# sds3_pcb_rev1.net
KiCad netlist of a schematic drawn in EAGLE
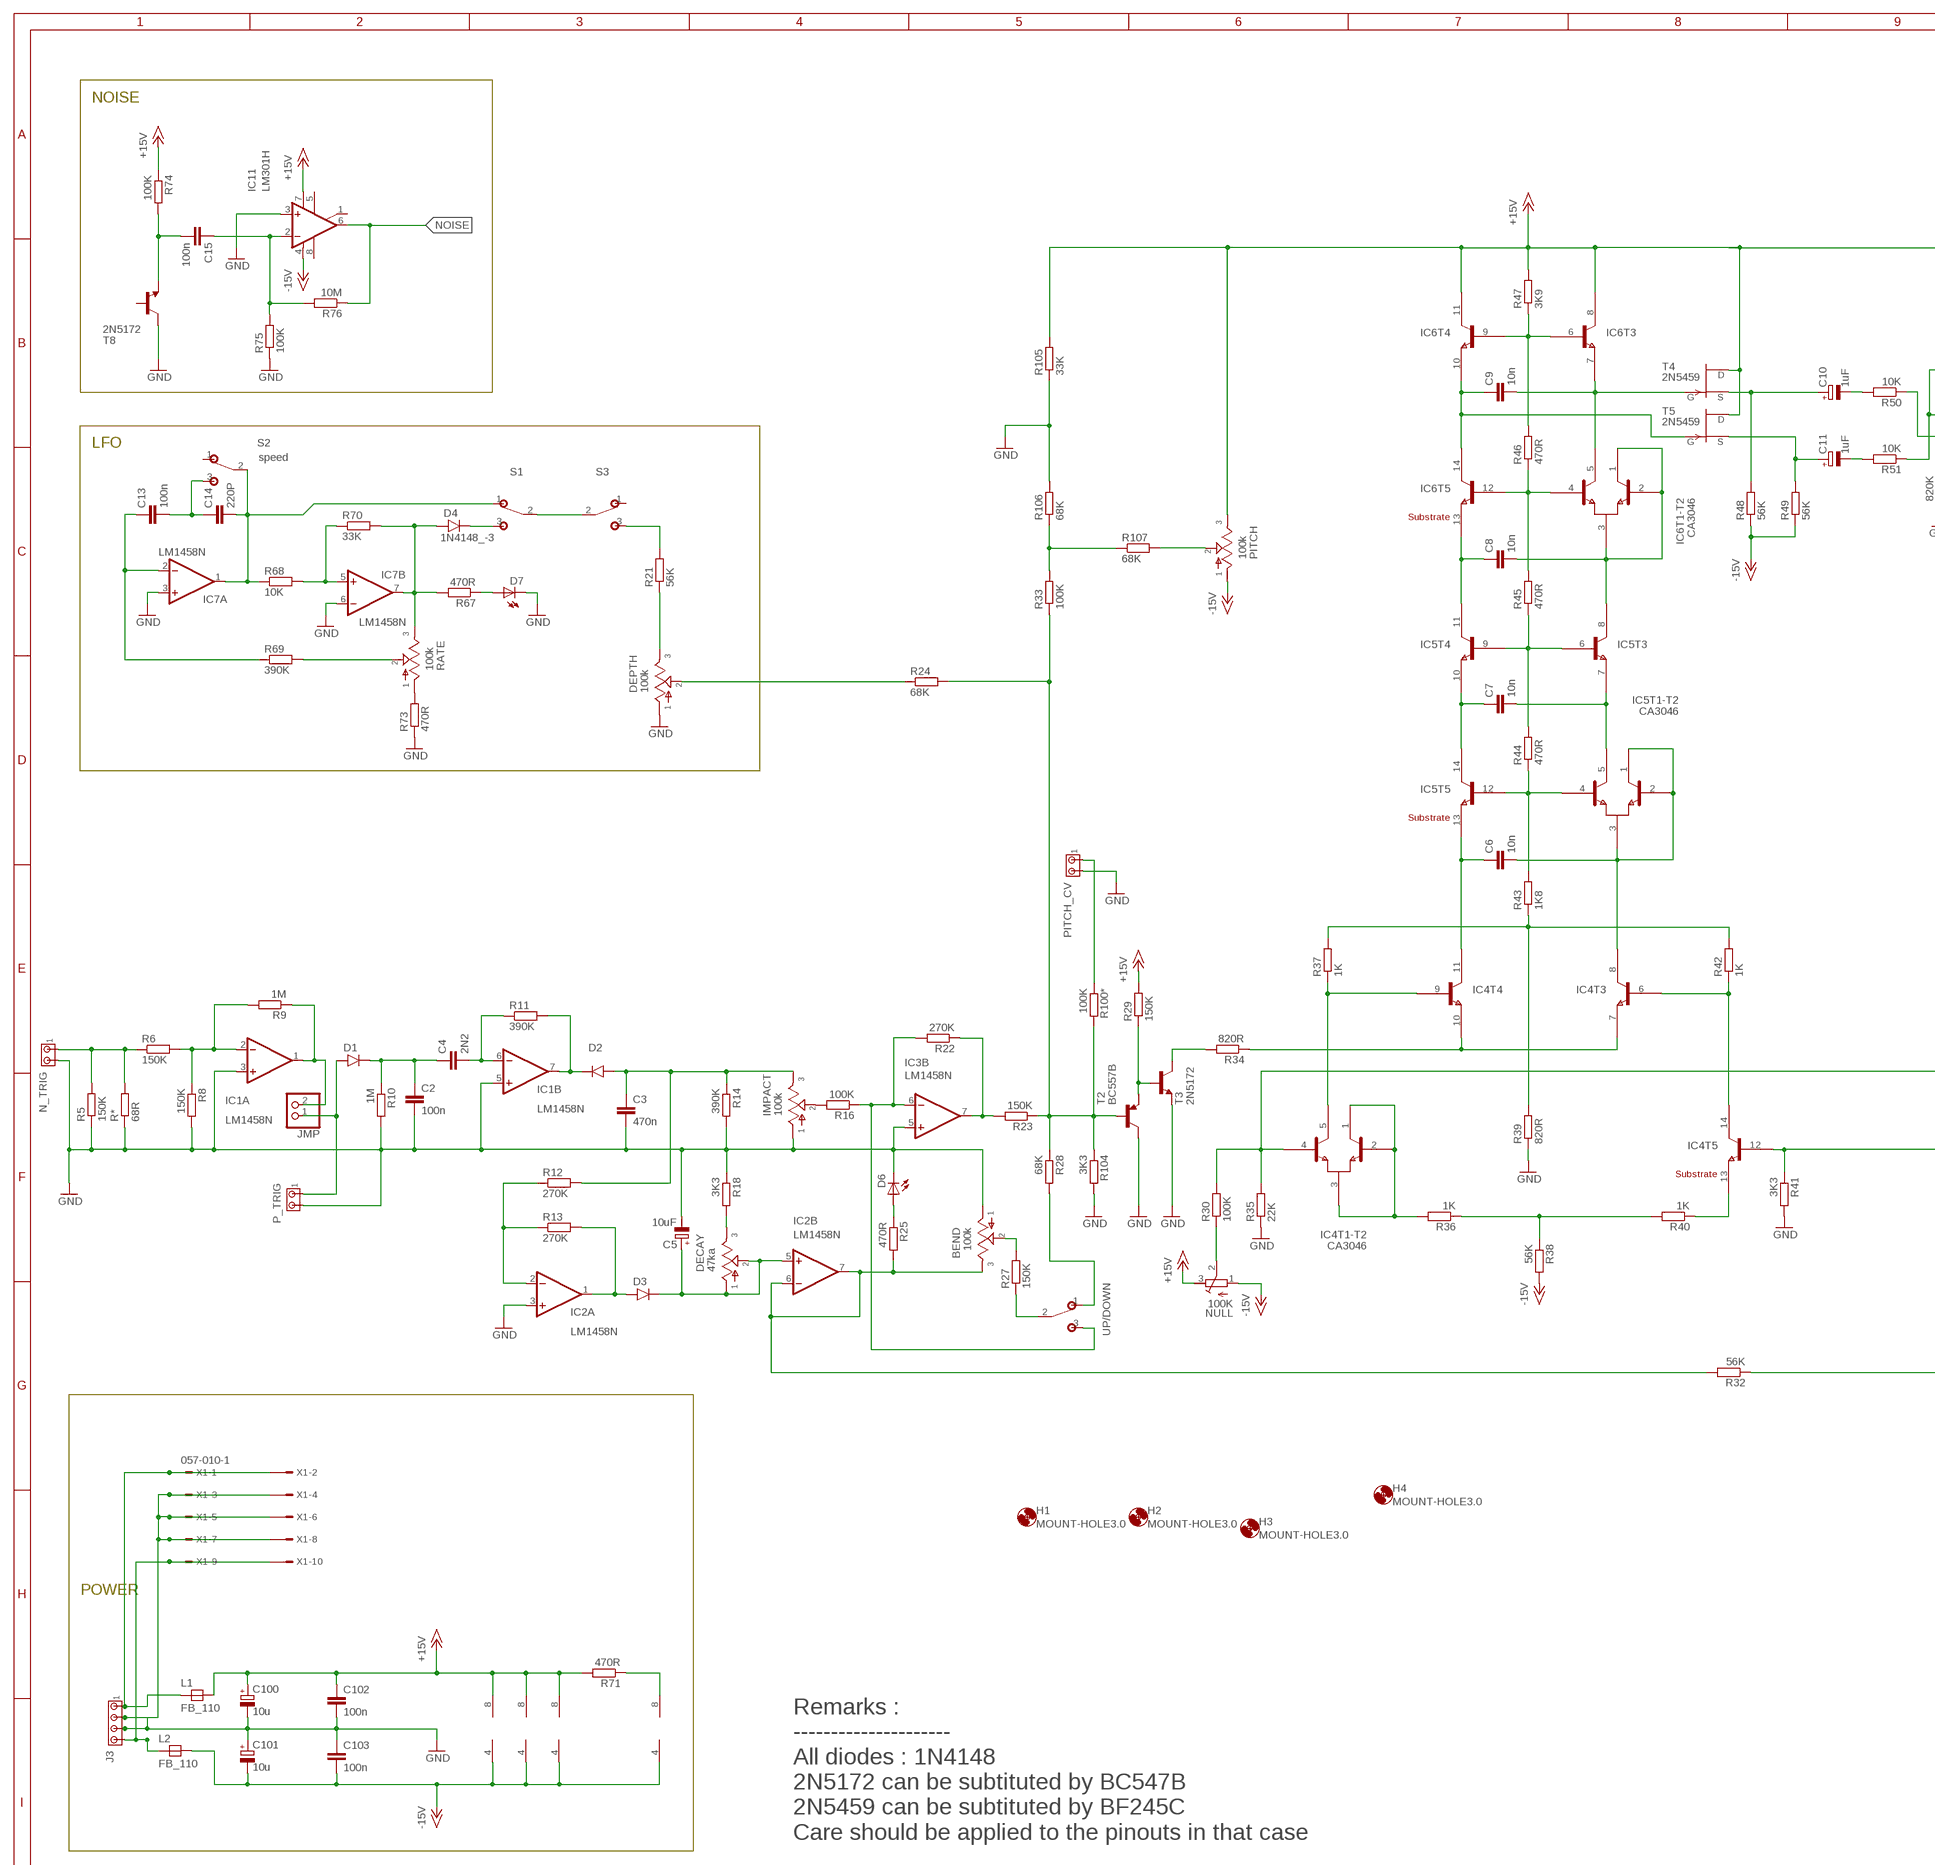
[diagram p0: schematic, sheet 1, part 1 of 2]
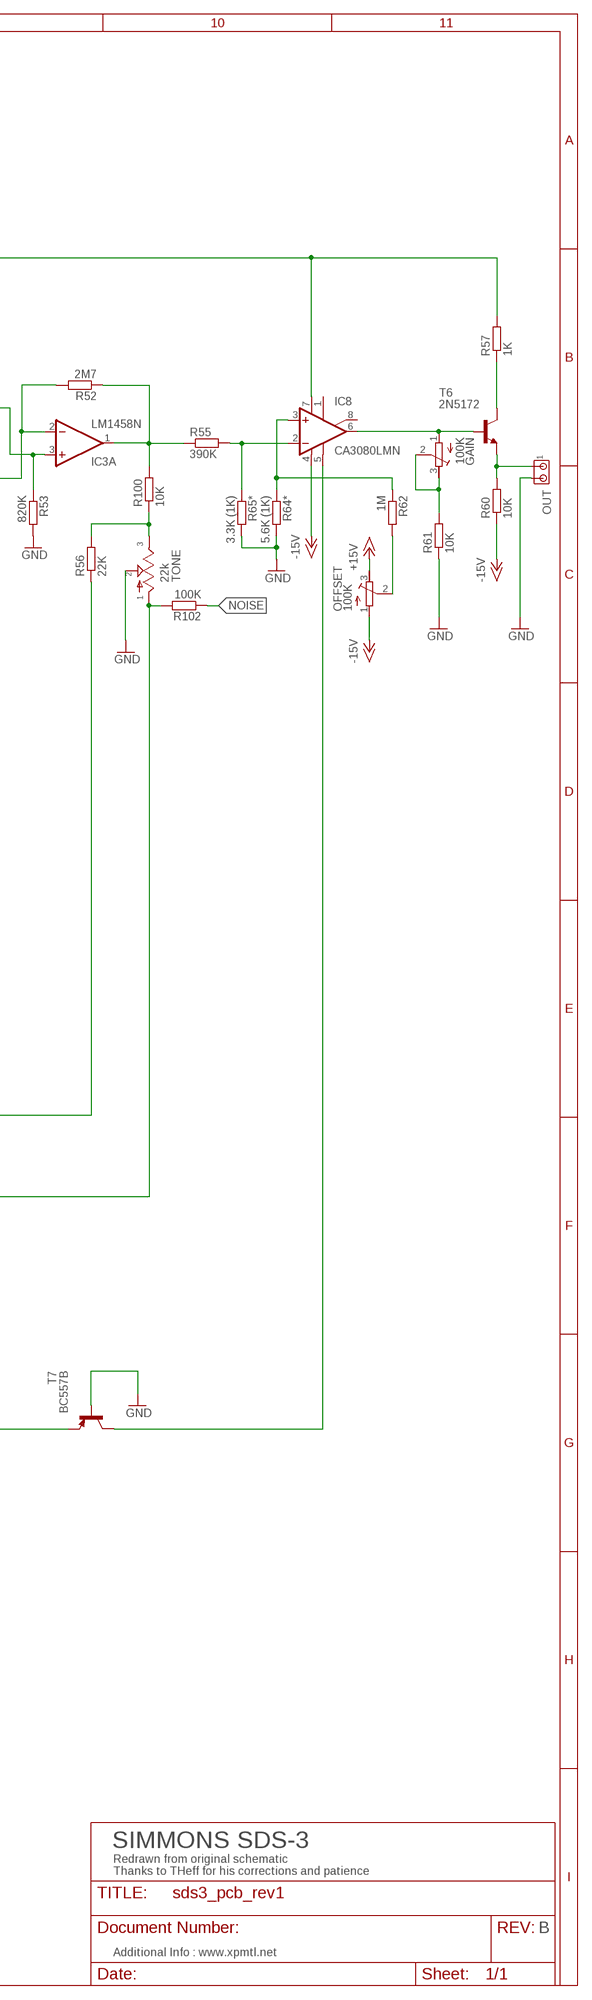
[diagram p1: schematic, sheet 1, part 2 of 2]

(export (version "E")
  (design (tool "Eeschema 10.0.6"))
  (components
    (comp (ref "BEND")
      (value "100k")
      (footprint "eagle-import:POT")
      (libsource (lib "eagle-import") (part "POT"))
    )
    (comp (ref "C2")
      (value "100n")
      (footprint "eagle-import:C050-025X075")
      (libsource (lib "eagle-import") (part "C-EU050-025X075"))
    )
    (comp (ref "C3")
      (value "470n")
      (footprint "eagle-import:C050-025X075")
      (libsource (lib "eagle-import") (part "C-EU050-025X075"))
    )
    (comp (ref "C4")
      (value "2N2")
      (footprint "eagle-import:C050-025X075")
      (libsource (lib "eagle-import") (part "C-EU050-025X075"))
    )
    (comp (ref "C5")
      (value "10uF")
      (footprint "eagle-import:E2,5-6")
      (libsource (lib "eagle-import") (part "CPOL-EUE2.5-6"))
    )
    (comp (ref "C6")
      (value "10n")
      (footprint "eagle-import:C050-025X075")
      (libsource (lib "eagle-import") (part "C-EU050-025X075"))
    )
    (comp (ref "C7")
      (value "10n")
      (footprint "eagle-import:C050-025X075")
      (libsource (lib "eagle-import") (part "C-EU050-025X075"))
    )
    (comp (ref "C8")
      (value "10n")
      (footprint "eagle-import:C050-025X075")
      (libsource (lib "eagle-import") (part "C-EU050-025X075"))
    )
    (comp (ref "C9")
      (value "10n")
      (footprint "eagle-import:C050-025X075")
      (libsource (lib "eagle-import") (part "C-EU050-025X075"))
    )
    (comp (ref "C10")
      (value "1uF")
      (footprint "eagle-import:E2,5-6")
      (libsource (lib "eagle-import") (part "CPOL-EUE2.5-6"))
    )
    (comp (ref "C11")
      (value "1uF")
      (footprint "eagle-import:E2,5-6")
      (libsource (lib "eagle-import") (part "CPOL-EUE2.5-6"))
    )
    (comp (ref "C13")
      (value "100n")
      (footprint "eagle-import:C050-025X075")
      (libsource (lib "eagle-import") (part "rcl_C-EU050-025X075"))
    )
    (comp (ref "C14")
      (value "220P")
      (footprint "eagle-import:C050-025X075")
      (libsource (lib "eagle-import") (part "rcl_C-EU050-025X075"))
    )
    (comp (ref "C15")
      (value "100n")
      (footprint "eagle-import:C050-025X075")
      (libsource (lib "eagle-import") (part "rcl_C-EU050-025X075"))
    )
    (comp (ref "C100")
      (value "10u")
      (footprint "eagle-import:B45181A")
      (libsource (lib "eagle-import") (part "rcl_CPOL-EUB45181A"))
    )
    (comp (ref "C101")
      (value "10u")
      (footprint "eagle-import:B45181A")
      (libsource (lib "eagle-import") (part "rcl_CPOL-EUB45181A"))
    )
    (comp (ref "C102")
      (value "100n")
      (footprint "eagle-import:C050-025X075")
      (libsource (lib "eagle-import") (part "rcl_C-EU050-025X075"))
    )
    (comp (ref "C103")
      (value "100n")
      (footprint "eagle-import:C050-025X075")
      (libsource (lib "eagle-import") (part "rcl_C-EU050-025X075"))
    )
    (comp (ref "D1")
      (value "1N4148_-3")
      (footprint "eagle-import:DO35-3")
      (libsource (lib "eagle-import") (part "1N4148_-3"))
    )
    (comp (ref "D2")
      (value "1N4148_-3")
      (footprint "eagle-import:DO35-3")
      (libsource (lib "eagle-import") (part "1N4148_-3"))
    )
    (comp (ref "D3")
      (value "1N4148_-3")
      (footprint "eagle-import:DO35-3")
      (libsource (lib "eagle-import") (part "1N4148_-3"))
    )
    (comp (ref "D4")
      (value "1N4148_-3")
      (footprint "eagle-import:DO35-3")
      (libsource (lib "eagle-import") (part "1N4148_-3"))
    )
    (comp (ref "D6")
      (value "LED5MM")
      (footprint "eagle-import:LED5MM")
      (libsource (lib "eagle-import") (part "LED5MM"))
    )
    (comp (ref "D7")
      (value "LED5MM")
      (footprint "eagle-import:LED5MM")
      (libsource (lib "eagle-import") (part "LED5MM"))
    )
    (comp (ref "DECAY")
      (value "47ka")
      (footprint "eagle-import:POT")
      (libsource (lib "eagle-import") (part "POT"))
    )
    (comp (ref "DEPTH")
      (value "100k")
      (footprint "eagle-import:POT")
      (libsource (lib "eagle-import") (part "POT"))
    )
    (comp (ref "GAIN")
      (value "100K")
      (footprint "eagle-import:RTRIM3296W")
      (libsource (lib "eagle-import") (part "R-TRIMM3296W"))
    )
    (comp (ref "H1")
      (value "MOUNT-HOLE3.0")
      (footprint "eagle-import:3,0")
      (libsource (lib "eagle-import") (part "MOUNT-HOLE3.0"))
    )
    (comp (ref "H2")
      (value "MOUNT-HOLE3.0")
      (footprint "eagle-import:3,0")
      (libsource (lib "eagle-import") (part "MOUNT-HOLE3.0"))
    )
    (comp (ref "H3")
      (value "MOUNT-HOLE3.0")
      (footprint "eagle-import:3,0")
      (libsource (lib "eagle-import") (part "MOUNT-HOLE3.0"))
    )
    (comp (ref "H4")
      (value "MOUNT-HOLE3.0")
      (footprint "eagle-import:3,0")
      (libsource (lib "eagle-import") (part "MOUNT-HOLE3.0"))
    )
    (comp (ref "IC1")
      (value "LM1458N")
      (footprint "eagle-import:DIL08")
      (libsource (lib "eagle-import") (part "1458NLM"))
    )
    (comp (ref "IC2")
      (value "LM1458N")
      (footprint "eagle-import:DIL08")
      (libsource (lib "eagle-import") (part "1458NLM"))
    )
    (comp (ref "IC3")
      (value "LM1458N")
      (footprint "eagle-import:DIL08")
      (libsource (lib "eagle-import") (part "1458NLM"))
    )
    (comp (ref "IC4")
      (value "CA3046")
      (footprint "eagle-import:DIL14")
      (libsource (lib "eagle-import") (part "CA3046"))
    )
    (comp (ref "IC5")
      (value "CA3046")
      (footprint "eagle-import:DIL14")
      (libsource (lib "eagle-import") (part "CA3046"))
    )
    (comp (ref "IC6")
      (value "CA3046")
      (footprint "eagle-import:DIL14")
      (libsource (lib "eagle-import") (part "CA3046"))
    )
    (comp (ref "IC7")
      (value "LM1458N")
      (footprint "eagle-import:DIL08")
      (libsource (lib "eagle-import") (part "1458NLM"))
    )
    (comp (ref "IC8")
      (value "CA3080LMN")
      (footprint "eagle-import:DIL08")
      (libsource (lib "eagle-import") (part "CA3080NLM"))
    )
    (comp (ref "IC11")
      (value "LM301H")
      (footprint "eagle-import:DIL08")
      (libsource (lib "eagle-import") (part "LM301H"))
    )
    (comp (ref "IMPACT")
      (value "100k")
      (footprint "eagle-import:POT")
      (libsource (lib "eagle-import") (part "POT"))
    )
    (comp (ref "J3")
      (value "MTA04-156")
      (footprint "eagle-import:1X4MTA")
      (libsource (lib "eagle-import") (part "MTA04-156"))
    )
    (comp (ref "JMP")
      (value "PINHD-1X2")
      (footprint "eagle-import:1X02")
      (libsource (lib "eagle-import") (part "PINHD-1X2"))
    )
    (comp (ref "L1")
      (value "FB_110")
      (footprint "eagle-import:FB-110")
      (libsource (lib "eagle-import") (part "FB_110"))
    )
    (comp (ref "L2")
      (value "FB_110")
      (footprint "eagle-import:FB-110")
      (libsource (lib "eagle-import") (part "FB_110"))
    )
    (comp (ref "NULL")
      (value "100K")
      (footprint "eagle-import:RTRIM3296W")
      (libsource (lib "eagle-import") (part "R-TRIMM3296W"))
    )
    (comp (ref "N_TRIG")
      (value "MTA02-100")
      (footprint "eagle-import:10X02MTA")
      (libsource (lib "eagle-import") (part "MTA02-100"))
    )
    (comp (ref "OFFSET")
      (value "100K")
      (footprint "eagle-import:RTRIM3296W")
      (libsource (lib "eagle-import") (part "R-TRIMM3296W"))
    )
    (comp (ref "OUT")
      (value "MTA02-100")
      (footprint "eagle-import:10X02MTA")
      (libsource (lib "eagle-import") (part "MTA02-100"))
    )
    (comp (ref "PITCH")
      (value "100k")
      (footprint "eagle-import:POT")
      (libsource (lib "eagle-import") (part "POT"))
    )
    (comp (ref "PITCH_CV")
      (value "MTA02-100")
      (footprint "eagle-import:10X02MTA")
      (libsource (lib "eagle-import") (part "MTA02-100"))
    )
    (comp (ref "P_TRIG")
      (value "MTA02-100")
      (footprint "eagle-import:10X02MTA")
      (libsource (lib "eagle-import") (part "MTA02-100"))
    )
    (comp (ref "R*")
      (value "68R")
      (footprint "eagle-import:0309V")
      (libsource (lib "eagle-import") (part "rcl_R-EU_0309/V"))
    )
    (comp (ref "R5")
      (value "150K")
      (footprint "eagle-import:0309V")
      (libsource (lib "eagle-import") (part "rcl_R-EU_0309/V"))
    )
    (comp (ref "R6")
      (value "150K")
      (footprint "eagle-import:0309V")
      (libsource (lib "eagle-import") (part "rcl_R-EU_0309/V"))
    )
    (comp (ref "R8")
      (value "150K")
      (footprint "eagle-import:0309V")
      (libsource (lib "eagle-import") (part "rcl_R-EU_0309/V"))
    )
    (comp (ref "R9")
      (value "1M")
      (footprint "eagle-import:0309V")
      (libsource (lib "eagle-import") (part "rcl_R-EU_0309/V"))
    )
    (comp (ref "R10")
      (value "1M")
      (footprint "eagle-import:0309V")
      (libsource (lib "eagle-import") (part "rcl_R-EU_0309/V"))
    )
    (comp (ref "R11")
      (value "390K")
      (footprint "eagle-import:0309V")
      (libsource (lib "eagle-import") (part "rcl_R-EU_0309/V"))
    )
    (comp (ref "R12")
      (value "270K")
      (footprint "eagle-import:0309V")
      (libsource (lib "eagle-import") (part "rcl_R-EU_0309/V"))
    )
    (comp (ref "R13")
      (value "270K")
      (footprint "eagle-import:0309V")
      (libsource (lib "eagle-import") (part "rcl_R-EU_0309/V"))
    )
    (comp (ref "R14")
      (value "390K")
      (footprint "eagle-import:0309V")
      (libsource (lib "eagle-import") (part "rcl_R-EU_0309/V"))
    )
    (comp (ref "R16")
      (value "100K")
      (footprint "eagle-import:0309V")
      (libsource (lib "eagle-import") (part "rcl_R-EU_0309/V"))
    )
    (comp (ref "R18")
      (value "3K3")
      (footprint "eagle-import:0309V")
      (libsource (lib "eagle-import") (part "rcl_R-EU_0309/V"))
    )
    (comp (ref "R21")
      (value "56K")
      (footprint "eagle-import:0309V")
      (libsource (lib "eagle-import") (part "rcl_R-EU_0309/V"))
    )
    (comp (ref "R22")
      (value "270K")
      (footprint "eagle-import:0309V")
      (libsource (lib "eagle-import") (part "rcl_R-EU_0309/V"))
    )
    (comp (ref "R23")
      (value "150K")
      (footprint "eagle-import:0309V")
      (libsource (lib "eagle-import") (part "rcl_R-EU_0309/V"))
    )
    (comp (ref "R24")
      (value "68K")
      (footprint "eagle-import:0309V")
      (libsource (lib "eagle-import") (part "rcl_R-EU_0309/V"))
    )
    (comp (ref "R25")
      (value "470R")
      (footprint "eagle-import:0309V")
      (libsource (lib "eagle-import") (part "rcl_R-EU_0309/V"))
    )
    (comp (ref "R27")
      (value "150K")
      (footprint "eagle-import:0309V")
      (libsource (lib "eagle-import") (part "rcl_R-EU_0309/V"))
    )
    (comp (ref "R28")
      (value "68K")
      (footprint "eagle-import:0309V")
      (libsource (lib "eagle-import") (part "rcl_R-EU_0309/V"))
    )
    (comp (ref "R29")
      (value "150K")
      (footprint "eagle-import:0309V")
      (libsource (lib "eagle-import") (part "rcl_R-EU_0309/V"))
    )
    (comp (ref "R30")
      (value "100K")
      (footprint "eagle-import:0309V")
      (libsource (lib "eagle-import") (part "rcl_R-EU_0309/V"))
    )
    (comp (ref "R32")
      (value "56K")
      (footprint "eagle-import:0309V")
      (libsource (lib "eagle-import") (part "rcl_R-EU_0309/V"))
    )
    (comp (ref "R33")
      (value "100K")
      (footprint "eagle-import:0309V")
      (libsource (lib "eagle-import") (part "rcl_R-EU_0309/V"))
    )
    (comp (ref "R34")
      (value "820R")
      (footprint "eagle-import:0309V")
      (libsource (lib "eagle-import") (part "rcl_R-EU_0309/V"))
    )
    (comp (ref "R35")
      (value "22K")
      (footprint "eagle-import:0309V")
      (libsource (lib "eagle-import") (part "rcl_R-EU_0309/V"))
    )
    (comp (ref "R36")
      (value "1K")
      (footprint "eagle-import:0309V")
      (libsource (lib "eagle-import") (part "rcl_R-EU_0309/V"))
    )
    (comp (ref "R37")
      (value "1K")
      (footprint "eagle-import:0309V")
      (libsource (lib "eagle-import") (part "rcl_R-EU_0309/V"))
    )
    (comp (ref "R38")
      (value "56K")
      (footprint "eagle-import:0309V")
      (libsource (lib "eagle-import") (part "rcl_R-EU_0309/V"))
    )
    (comp (ref "R39")
      (value "820R")
      (footprint "eagle-import:0309V")
      (libsource (lib "eagle-import") (part "rcl_R-EU_0309/V"))
    )
    (comp (ref "R40")
      (value "1K")
      (footprint "eagle-import:0309V")
      (libsource (lib "eagle-import") (part "rcl_R-EU_0309/V"))
    )
    (comp (ref "R41")
      (value "3K3")
      (footprint "eagle-import:0309V")
      (libsource (lib "eagle-import") (part "rcl_R-EU_0309/V"))
    )
    (comp (ref "R42")
      (value "1K")
      (footprint "eagle-import:0309V")
      (libsource (lib "eagle-import") (part "rcl_R-EU_0309/V"))
    )
    (comp (ref "R43")
      (value "1K8")
      (footprint "eagle-import:0309V")
      (libsource (lib "eagle-import") (part "rcl_R-EU_0309/V"))
    )
    (comp (ref "R44")
      (value "470R")
      (footprint "eagle-import:0309V")
      (libsource (lib "eagle-import") (part "rcl_R-EU_0309/V"))
    )
    (comp (ref "R45")
      (value "470R")
      (footprint "eagle-import:0309V")
      (libsource (lib "eagle-import") (part "rcl_R-EU_0309/V"))
    )
    (comp (ref "R46")
      (value "470R")
      (footprint "eagle-import:0309V")
      (libsource (lib "eagle-import") (part "rcl_R-EU_0309/V"))
    )
    (comp (ref "R47")
      (value "3K9")
      (footprint "eagle-import:0309V")
      (libsource (lib "eagle-import") (part "rcl_R-EU_0309/V"))
    )
    (comp (ref "R48")
      (value "56K")
      (footprint "eagle-import:0309V")
      (libsource (lib "eagle-import") (part "rcl_R-EU_0309/V"))
    )
    (comp (ref "R49")
      (value "56K")
      (footprint "eagle-import:0309V")
      (libsource (lib "eagle-import") (part "rcl_R-EU_0309/V"))
    )
    (comp (ref "R50")
      (value "10K")
      (footprint "eagle-import:0309V")
      (libsource (lib "eagle-import") (part "rcl_R-EU_0309/V"))
    )
    (comp (ref "R51")
      (value "10K")
      (footprint "eagle-import:0309V")
      (libsource (lib "eagle-import") (part "rcl_R-EU_0309/V"))
    )
    (comp (ref "R52")
      (value "2M7")
      (footprint "eagle-import:0309V")
      (libsource (lib "eagle-import") (part "rcl_R-EU_0309/V"))
    )
    (comp (ref "R53")
      (value "820K")
      (footprint "eagle-import:0309V")
      (libsource (lib "eagle-import") (part "rcl_R-EU_0309/V"))
    )
    (comp (ref "R55")
      (value "390K")
      (footprint "eagle-import:0309V")
      (libsource (lib "eagle-import") (part "rcl_R-EU_0309/V"))
    )
    (comp (ref "R56")
      (value "22K")
      (footprint "eagle-import:0309V")
      (libsource (lib "eagle-import") (part "rcl_R-EU_0309/V"))
    )
    (comp (ref "R57")
      (value "1K")
      (footprint "eagle-import:0309V")
      (libsource (lib "eagle-import") (part "rcl_R-EU_0309/V"))
    )
    (comp (ref "R60")
      (value "10K")
      (footprint "eagle-import:0309V")
      (libsource (lib "eagle-import") (part "rcl_R-EU_0309/V"))
    )
    (comp (ref "R61")
      (value "10K")
      (footprint "eagle-import:0309V")
      (libsource (lib "eagle-import") (part "rcl_R-EU_0309/V"))
    )
    (comp (ref "R62")
      (value "1M")
      (footprint "eagle-import:0309V")
      (libsource (lib "eagle-import") (part "rcl_R-EU_0309/V"))
    )
    (comp (ref "R64*")
      (value "5.6K (1K)")
      (footprint "eagle-import:0309V")
      (libsource (lib "eagle-import") (part "rcl_R-EU_0309/V"))
    )
    (comp (ref "R65*")
      (value "3.3K (1K)")
      (footprint "eagle-import:0309V")
      (libsource (lib "eagle-import") (part "rcl_R-EU_0309/V"))
    )
    (comp (ref "R67")
      (value "470R")
      (footprint "eagle-import:0309V")
      (libsource (lib "eagle-import") (part "rcl_R-EU_0309/V"))
    )
    (comp (ref "R68")
      (value "10K")
      (footprint "eagle-import:0309V")
      (libsource (lib "eagle-import") (part "rcl_R-EU_0309/V"))
    )
    (comp (ref "R69")
      (value "390K")
      (footprint "eagle-import:0309V")
      (libsource (lib "eagle-import") (part "rcl_R-EU_0309/V"))
    )
    (comp (ref "R70")
      (value "33K")
      (footprint "eagle-import:0309V")
      (libsource (lib "eagle-import") (part "rcl_R-EU_0309/V"))
    )
    (comp (ref "R71")
      (value "470R")
      (footprint "eagle-import:0309V")
      (libsource (lib "eagle-import") (part "rcl_R-EU_0309/V"))
    )
    (comp (ref "R73")
      (value "470R")
      (footprint "eagle-import:0309V")
      (libsource (lib "eagle-import") (part "rcl_R-EU_0309/V"))
    )
    (comp (ref "R74")
      (value "100K")
      (footprint "eagle-import:0309V")
      (libsource (lib "eagle-import") (part "rcl_R-EU_0309/V"))
    )
    (comp (ref "R75")
      (value "100K")
      (footprint "eagle-import:0309V")
      (libsource (lib "eagle-import") (part "rcl_R-EU_0309/V"))
    )
    (comp (ref "R76")
      (value "10M")
      (footprint "eagle-import:0309V")
      (libsource (lib "eagle-import") (part "rcl_R-EU_0309/V"))
    )
    (comp (ref "R100")
      (value "10K")
      (footprint "eagle-import:0309V")
      (libsource (lib "eagle-import") (part "rcl_R-EU_0309/V"))
    )
    (comp (ref "R100*")
      (value "100K")
      (footprint "eagle-import:0309V")
      (libsource (lib "eagle-import") (part "rcl_R-EU_0309/V"))
    )
    (comp (ref "R102")
      (value "100K")
      (footprint "eagle-import:0309V")
      (libsource (lib "eagle-import") (part "rcl_R-EU_0309/V"))
    )
    (comp (ref "R104")
      (value "3K3")
      (footprint "eagle-import:0309V")
      (libsource (lib "eagle-import") (part "rcl_R-EU_0309/V"))
    )
    (comp (ref "R105")
      (value "33K")
      (footprint "eagle-import:0309V")
      (libsource (lib "eagle-import") (part "rcl_R-EU_0309/V"))
    )
    (comp (ref "R106")
      (value "68K")
      (footprint "eagle-import:0309V")
      (libsource (lib "eagle-import") (part "rcl_R-EU_0309/V"))
    )
    (comp (ref "R107")
      (value "68K")
      (footprint "eagle-import:0309V")
      (libsource (lib "eagle-import") (part "rcl_R-EU_0309/V"))
    )
    (comp (ref "RATE")
      (value "100k")
      (footprint "eagle-import:POT")
      (libsource (lib "eagle-import") (part "POT"))
    )
    (comp (ref "S1")
      (value "shape")
      (footprint "eagle-import:SPDT")
      (libsource (lib "eagle-import") (part "SPDTPADS"))
    )
    (comp (ref "S2")
      (value "speed")
      (footprint "eagle-import:SPDT")
      (libsource (lib "eagle-import") (part "SPDTPADS"))
    )
    (comp (ref "S3")
      (value "on/off")
      (footprint "eagle-import:SPDT")
      (libsource (lib "eagle-import") (part "SPDTPADS"))
    )
    (comp (ref "T2")
      (value "BC557B")
      (footprint "eagle-import:TO92-EBC")
      (libsource (lib "eagle-import") (part "BC557B"))
    )
    (comp (ref "T3")
      (value "2N5172")
      (footprint "eagle-import:TO92-LINE")
      (libsource (lib "eagle-import") (part "2N5172"))
    )
    (comp (ref "T4")
      (value "2N5459")
      (footprint "eagle-import:TO92-FET2")
      (libsource (lib "eagle-import") (part "2N5459"))
    )
    (comp (ref "T5")
      (value "2N5459")
      (footprint "eagle-import:TO92-FET2")
      (libsource (lib "eagle-import") (part "2N5459"))
    )
    (comp (ref "T6")
      (value "2N5172")
      (footprint "eagle-import:TO92-LINE")
      (libsource (lib "eagle-import") (part "2N5172"))
    )
    (comp (ref "T7")
      (value "BC557B")
      (footprint "eagle-import:TO92-EBC")
      (libsource (lib "eagle-import") (part "BC557B"))
    )
    (comp (ref "T8")
      (value "2N5172")
      (footprint "eagle-import:TO92-LINE")
      (libsource (lib "eagle-import") (part "2N5172"))
    )
    (comp (ref "TONE")
      (value "22k")
      (footprint "eagle-import:POT")
      (libsource (lib "eagle-import") (part "POT"))
    )
    (comp (ref "UP/DOWN")
      (value "SPDTPADS")
      (footprint "eagle-import:SPDT")
      (libsource (lib "eagle-import") (part "SPDTPADS"))
    )
    (comp (ref "X1")
      (value "057-010-1")
      (footprint "eagle-import:057-010-1")
      (libsource (lib "eagle-import") (part "057-010-1"))
    )
  )
  (nets
    (net (code "1") (name "+15V") (class "Default")
      (node (ref "C100") (pin "+") (pinfunction "+_+") (pintype "passive"))
      (node (ref "C102") (pin "1") (pinfunction "1_1") (pintype "passive"))
      (node (ref "IC1") (pin "8") (pinfunction "V+_8") (pintype "power_in"))
      (node (ref "IC11") (pin "7") (pinfunction "V+_7") (pintype "power_in"))
      (node (ref "IC2") (pin "8") (pinfunction "V+_8") (pintype "power_in"))
      (node (ref "IC3") (pin "8") (pinfunction "V+_8") (pintype "power_in"))
      (node (ref "IC6") (pin "11") (pinfunction "C_11") (pintype "passive"))
      (node (ref "IC6") (pin "8") (pinfunction "C_8") (pintype "passive"))
      (node (ref "IC8") (pin "7") (pinfunction "V+_7") (pintype "power_in"))
      (node (ref "L1") (pin "2") (pinfunction "2_2") (pintype "passive"))
      (node (ref "NULL") (pin "3") (pinfunction "E_3") (pintype "passive"))
      (node (ref "OFFSET") (pin "3") (pinfunction "E_3") (pintype "passive"))
      (node (ref "PITCH") (pin "3") (pinfunction "3_3") (pintype "passive"))
      (node (ref "R105") (pin "2") (pinfunction "2_2") (pintype "passive"))
      (node (ref "R29") (pin "2") (pinfunction "2_2") (pintype "passive"))
      (node (ref "R47") (pin "2") (pinfunction "2_2") (pintype "passive"))
      (node (ref "R57") (pin "2") (pinfunction "2_2") (pintype "passive"))
      (node (ref "R71") (pin "2") (pinfunction "2_2") (pintype "passive"))
      (node (ref "R74") (pin "1") (pinfunction "1_1") (pintype "passive"))
      (node (ref "T4") (pin "D") (pinfunction "D_D") (pintype "passive"))
      (node (ref "T5") (pin "D") (pinfunction "D_D") (pintype "passive"))
    )
    (net (code "2") (name "-15V") (class "Default")
      (node (ref "C101") (pin "-") (pinfunction "-_-") (pintype "passive"))
      (node (ref "C103") (pin "2") (pinfunction "2_2") (pintype "passive"))
      (node (ref "IC1") (pin "4") (pinfunction "V-_4") (pintype "power_in"))
      (node (ref "IC11") (pin "4") (pinfunction "V-_4") (pintype "power_in"))
      (node (ref "IC2") (pin "4") (pinfunction "V-_4") (pintype "power_in"))
      (node (ref "IC3") (pin "4") (pinfunction "V-_4") (pintype "power_in"))
      (node (ref "IC7") (pin "4") (pinfunction "V-_4") (pintype "power_in"))
      (node (ref "IC8") (pin "4") (pinfunction "V-_4") (pintype "power_in"))
      (node (ref "L2") (pin "2") (pinfunction "2_2") (pintype "passive"))
      (node (ref "NULL") (pin "1") (pinfunction "A_1") (pintype "passive"))
      (node (ref "OFFSET") (pin "1") (pinfunction "A_1") (pintype "passive"))
      (node (ref "PITCH") (pin "1") (pinfunction "1_1") (pintype "passive"))
      (node (ref "R38") (pin "2") (pinfunction "2_2") (pintype "passive"))
      (node (ref "R48") (pin "1") (pinfunction "1_1") (pintype "passive"))
      (node (ref "R49") (pin "1") (pinfunction "1_1") (pintype "passive"))
      (node (ref "R60") (pin "1") (pinfunction "1_1") (pintype "passive"))
    )
    (net (code "3") (name "GND") (class "Default")
      (node (ref "BEND") (pin "1") (pinfunction "1_1") (pintype "passive"))
      (node (ref "C100") (pin "-") (pinfunction "-_-") (pintype "passive"))
      (node (ref "C101") (pin "+") (pinfunction "+_+") (pintype "passive"))
      (node (ref "C102") (pin "2") (pinfunction "2_2") (pintype "passive"))
      (node (ref "C103") (pin "1") (pinfunction "1_1") (pintype "passive"))
      (node (ref "C2") (pin "2") (pinfunction "2_2") (pintype "passive"))
      (node (ref "C3") (pin "2") (pinfunction "2_2") (pintype "passive"))
      (node (ref "C5") (pin "-") (pinfunction "-_-") (pintype "passive"))
      (node (ref "D6") (pin "K") (pinfunction "C_K") (pintype "passive"))
      (node (ref "D7") (pin "K") (pinfunction "C_K") (pintype "passive"))
      (node (ref "DEPTH") (pin "1") (pinfunction "1_1") (pintype "passive"))
      (node (ref "IC1") (pin "3") (pinfunction "+IN_3") (pintype "input"))
      (node (ref "IC1") (pin "5") (pinfunction "+IN_5") (pintype "input"))
      (node (ref "IC11") (pin "3") (pinfunction "+IN_3") (pintype "input"))
      (node (ref "IC2") (pin "3") (pinfunction "+IN_3") (pintype "input"))
      (node (ref "IC3") (pin "5") (pinfunction "+IN_5") (pintype "input"))
      (node (ref "IC7") (pin "3") (pinfunction "+IN_3") (pintype "input"))
      (node (ref "IC7") (pin "6") (pinfunction "-IN_6") (pintype "input"))
      (node (ref "IMPACT") (pin "1") (pinfunction "1_1") (pintype "passive"))
      (node (ref "J3") (pin "2") (pinfunction "2_2") (pintype "passive"))
      (node (ref "J3") (pin "3") (pinfunction "3_3") (pintype "passive"))
      (node (ref "N_TRIG") (pin "2") (pinfunction "2_2") (pintype "passive"))
      (node (ref "OUT") (pin "2") (pinfunction "2_2") (pintype "passive"))
      (node (ref "PITCH_CV") (pin "2") (pinfunction "2_2") (pintype "passive"))
      (node (ref "P_TRIG") (pin "2") (pinfunction "2_2") (pintype "passive"))
      (node (ref "R*") (pin "1") (pinfunction "1_1") (pintype "passive"))
      (node (ref "R10") (pin "2") (pinfunction "2_2") (pintype "passive"))
      (node (ref "R104") (pin "2") (pinfunction "2_2") (pintype "passive"))
      (node (ref "R105") (pin "1") (pinfunction "1_1") (pintype "passive"))
      (node (ref "R106") (pin "2") (pinfunction "2_2") (pintype "passive"))
      (node (ref "R14") (pin "2") (pinfunction "2_2") (pintype "passive"))
      (node (ref "R18") (pin "1") (pinfunction "1_1") (pintype "passive"))
      (node (ref "R35") (pin "1") (pinfunction "1_1") (pintype "passive"))
      (node (ref "R39") (pin "1") (pinfunction "1_1") (pintype "passive"))
      (node (ref "R41") (pin "2") (pinfunction "2_2") (pintype "passive"))
      (node (ref "R5") (pin "1") (pinfunction "1_1") (pintype "passive"))
      (node (ref "R53") (pin "2") (pinfunction "2_2") (pintype "passive"))
      (node (ref "R61") (pin "1") (pinfunction "1_1") (pintype "passive"))
      (node (ref "R64*") (pin "2") (pinfunction "2_2") (pintype "passive"))
      (node (ref "R65*") (pin "2") (pinfunction "2_2") (pintype "passive"))
      (node (ref "R73") (pin "1") (pinfunction "1_1") (pintype "passive"))
      (node (ref "R75") (pin "1") (pinfunction "1_1") (pintype "passive"))
      (node (ref "R8") (pin "2") (pinfunction "2_2") (pintype "passive"))
      (node (ref "T2") (pin "C") (pinfunction "C_C") (pintype "passive"))
      (node (ref "T3") (pin "E") (pinfunction "E_E") (pintype "passive"))
      (node (ref "T7") (pin "B") (pinfunction "B_B") (pintype "passive"))
      (node (ref "T8") (pin "C") (pinfunction "C_C") (pintype "passive"))
      (node (ref "TONE") (pin "2") (pinfunction "2_2") (pintype "passive"))
      (node (ref "X1") (pin "3") (pinfunction "S_3") (pintype "passive"))
      (node (ref "X1") (pin "4") (pinfunction "S_4") (pintype "passive"))
      (node (ref "X1") (pin "5") (pinfunction "S_5") (pintype "passive"))
      (node (ref "X1") (pin "6") (pinfunction "S_6") (pintype "passive"))
      (node (ref "X1") (pin "7") (pinfunction "S_7") (pintype "passive"))
      (node (ref "X1") (pin "8") (pinfunction "S_8") (pintype "passive"))
    )
    (net (code "4") (name "NOISE") (class "Default")
      (node (ref "IC11") (pin "6") (pinfunction "OUT_6") (pintype "output"))
      (node (ref "R102") (pin "1") (pinfunction "1_1") (pintype "passive"))
      (node (ref "R76") (pin "1") (pinfunction "1_1") (pintype "passive"))
    )
    (net (code "5") (name "Net-(BEND-Pad2)") (class "Default")
      (node (ref "BEND") (pin "2") (pinfunction "2_2") (pintype "passive"))
      (node (ref "R27") (pin "2") (pinfunction "2_2") (pintype "passive"))
    )
    (net (code "6") (name "Net-(C2-Pad1)") (class "Default")
      (node (ref "C2") (pin "1") (pinfunction "1_1") (pintype "passive"))
      (node (ref "C4") (pin "1") (pinfunction "1_1") (pintype "passive"))
      (node (ref "D1") (pin "C") (pinfunction "C_C") (pintype "passive"))
      (node (ref "R10") (pin "1") (pinfunction "1_1") (pintype "passive"))
    )
    (net (code "7") (name "Net-(C3-Pad1)") (class "Default")
      (node (ref "C3") (pin "1") (pinfunction "1_1") (pintype "passive"))
      (node (ref "D2") (pin "A") (pinfunction "A_A") (pintype "passive"))
      (node (ref "IMPACT") (pin "3") (pinfunction "3_3") (pintype "passive"))
      (node (ref "R12") (pin "2") (pinfunction "2_2") (pintype "passive"))
      (node (ref "R14") (pin "1") (pinfunction "1_1") (pintype "passive"))
    )
    (net (code "8") (name "Net-(C10-Pad+)") (class "Default")
      (node (ref "C10") (pin "+") (pinfunction "+_+") (pintype "passive"))
      (node (ref "R48") (pin "2") (pinfunction "2_2") (pintype "passive"))
      (node (ref "T4") (pin "S") (pinfunction "S_S") (pintype "passive"))
    )
    (net (code "9") (name "Net-(C10-Pad-)") (class "Default")
      (node (ref "C10") (pin "-") (pinfunction "-_-") (pintype "passive"))
      (node (ref "R50") (pin "2") (pinfunction "2_2") (pintype "passive"))
    )
    (net (code "10") (name "Net-(C11-Pad+)") (class "Default")
      (node (ref "C11") (pin "+") (pinfunction "+_+") (pintype "passive"))
      (node (ref "R49") (pin "2") (pinfunction "2_2") (pintype "passive"))
      (node (ref "T5") (pin "S") (pinfunction "S_S") (pintype "passive"))
    )
    (net (code "11") (name "Net-(C11-Pad-)") (class "Default")
      (node (ref "C11") (pin "-") (pinfunction "-_-") (pintype "passive"))
      (node (ref "R51") (pin "2") (pinfunction "2_2") (pintype "passive"))
    )
    (net (code "12") (name "Net-(C15-Pad2)") (class "Default")
      (node (ref "C15") (pin "2") (pinfunction "2_2") (pintype "passive"))
      (node (ref "R74") (pin "2") (pinfunction "2_2") (pintype "passive"))
      (node (ref "T8") (pin "E") (pinfunction "E_E") (pintype "passive"))
    )
    (net (code "13") (name "Net-(D1-PadA)") (class "Default")
      (node (ref "D1") (pin "A") (pinfunction "A_A") (pintype "passive"))
      (node (ref "JMP") (pin "1") (pinfunction "1_1") (pintype "passive"))
      (node (ref "P_TRIG") (pin "1") (pinfunction "1_1") (pintype "passive"))
    )
    (net (code "14") (name "Net-(D6-PadA)") (class "Default")
      (node (ref "D6") (pin "A") (pinfunction "A_A") (pintype "passive"))
      (node (ref "R25") (pin "1") (pinfunction "1_1") (pintype "passive"))
    )
    (net (code "15") (name "Net-(D7-PadA)") (class "Default")
      (node (ref "D7") (pin "A") (pinfunction "A_A") (pintype "passive"))
      (node (ref "R67") (pin "1") (pinfunction "1_1") (pintype "passive"))
    )
    (net (code "16") (name "Net-(DECAY-Pad3)") (class "Default")
      (node (ref "DECAY") (pin "3") (pinfunction "3_3") (pintype "passive"))
      (node (ref "R18") (pin "2") (pinfunction "2_2") (pintype "passive"))
    )
    (net (code "17") (name "Net-(DEPTH-Pad2)") (class "Default")
      (node (ref "DEPTH") (pin "2") (pinfunction "2_2") (pintype "passive"))
      (node (ref "R24") (pin "1") (pinfunction "1_1") (pintype "passive"))
    )
    (net (code "18") (name "Net-(DEPTH-Pad3)") (class "Default")
      (node (ref "DEPTH") (pin "3") (pinfunction "3_3") (pintype "passive"))
      (node (ref "R21") (pin "1") (pinfunction "1_1") (pintype "passive"))
    )
    (net (code "19") (name "Net-(GAIN-A)") (class "Default")
      (node (ref "GAIN") (pin "1") (pinfunction "A_1") (pintype "passive"))
      (node (ref "IC8") (pin "6") (pinfunction "OUT_6") (pintype "output"))
      (node (ref "T6") (pin "B") (pinfunction "B_B") (pintype "passive"))
    )
    (net (code "20") (name "Net-(GAIN-E)") (class "Default")
      (node (ref "GAIN") (pin "2") (pinfunction "S_2") (pintype "passive"))
      (node (ref "GAIN") (pin "3") (pinfunction "E_3") (pintype "passive"))
      (node (ref "R61") (pin "2") (pinfunction "2_2") (pintype "passive"))
    )
    (net (code "21") (name "Net-(IC1A--IN)") (class "Default")
      (node (ref "IC1") (pin "2") (pinfunction "-IN_2") (pintype "input"))
      (node (ref "R6") (pin "2") (pinfunction "2_2") (pintype "passive"))
      (node (ref "R8") (pin "1") (pinfunction "1_1") (pintype "passive"))
      (node (ref "R9") (pin "2") (pinfunction "2_2") (pintype "passive"))
    )
    (net (code "22") (name "Net-(IC1A-OUT)") (class "Default")
      (node (ref "IC1") (pin "1") (pinfunction "OUT_1") (pintype "output"))
      (node (ref "JMP") (pin "2") (pinfunction "2_2") (pintype "passive"))
      (node (ref "R9") (pin "1") (pinfunction "1_1") (pintype "passive"))
    )
    (net (code "23") (name "Net-(IC1B--IN)") (class "Default")
      (node (ref "C4") (pin "2") (pinfunction "2_2") (pintype "passive"))
      (node (ref "IC1") (pin "6") (pinfunction "-IN_6") (pintype "input"))
      (node (ref "R11") (pin "1") (pinfunction "1_1") (pintype "passive"))
    )
    (net (code "24") (name "Net-(IC1B-OUT)") (class "Default")
      (node (ref "D2") (pin "C") (pinfunction "C_C") (pintype "passive"))
      (node (ref "IC1") (pin "7") (pinfunction "OUT_7") (pintype "output"))
      (node (ref "R11") (pin "2") (pinfunction "2_2") (pintype "passive"))
    )
    (net (code "25") (name "Net-(IC2A--IN)") (class "Default")
      (node (ref "IC2") (pin "2") (pinfunction "-IN_2") (pintype "input"))
      (node (ref "R12") (pin "1") (pinfunction "1_1") (pintype "passive"))
      (node (ref "R13") (pin "1") (pinfunction "1_1") (pintype "passive"))
    )
    (net (code "26") (name "Net-(IC2A-OUT)") (class "Default")
      (node (ref "D3") (pin "A") (pinfunction "A_A") (pintype "passive"))
      (node (ref "IC2") (pin "1") (pinfunction "OUT_1") (pintype "output"))
      (node (ref "R13") (pin "2") (pinfunction "2_2") (pintype "passive"))
    )
    (net (code "27") (name "Net-(IC2B-+IN)") (class "Default")
      (node (ref "C5") (pin "+") (pinfunction "+_+") (pintype "passive"))
      (node (ref "D3") (pin "C") (pinfunction "C_C") (pintype "passive"))
      (node (ref "DECAY") (pin "1") (pinfunction "1_1") (pintype "passive"))
      (node (ref "DECAY") (pin "2") (pinfunction "2_2") (pintype "passive"))
      (node (ref "IC2") (pin "5") (pinfunction "+IN_5") (pintype "input"))
    )
    (net (code "28") (name "Net-(IC2B--IN)") (class "Default")
      (node (ref "BEND") (pin "3") (pinfunction "3_3") (pintype "passive"))
      (node (ref "IC2") (pin "6") (pinfunction "-IN_6") (pintype "input"))
      (node (ref "IC2") (pin "7") (pinfunction "OUT_7") (pintype "output"))
      (node (ref "R25") (pin "2") (pinfunction "2_2") (pintype "passive"))
      (node (ref "R32") (pin "2") (pinfunction "2_2") (pintype "passive"))
    )
    (net (code "29") (name "Net-(IC3A-+IN)") (class "Default")
      (node (ref "IC3") (pin "3") (pinfunction "+IN_3") (pintype "input"))
      (node (ref "R50") (pin "1") (pinfunction "1_1") (pintype "passive"))
      (node (ref "R53") (pin "1") (pinfunction "1_1") (pintype "passive"))
    )
    (net (code "30") (name "Net-(IC3A--IN)") (class "Default")
      (node (ref "IC3") (pin "2") (pinfunction "-IN_2") (pintype "input"))
      (node (ref "R51") (pin "1") (pinfunction "1_1") (pintype "passive"))
      (node (ref "R52") (pin "2") (pinfunction "2_2") (pintype "passive"))
    )
    (net (code "31") (name "Net-(IC3A-OUT)") (class "Default")
      (node (ref "IC3") (pin "1") (pinfunction "OUT_1") (pintype "output"))
      (node (ref "R100") (pin "2") (pinfunction "2_2") (pintype "passive"))
      (node (ref "R52") (pin "1") (pinfunction "1_1") (pintype "passive"))
      (node (ref "R55") (pin "1") (pinfunction "1_1") (pintype "passive"))
    )
    (net (code "32") (name "Net-(IC3B--IN)") (class "Default")
      (node (ref "IC3") (pin "6") (pinfunction "-IN_6") (pintype "input"))
      (node (ref "R16") (pin "1") (pinfunction "1_1") (pintype "passive"))
      (node (ref "R22") (pin "2") (pinfunction "2_2") (pintype "passive"))
      (node (ref "UP/DOWN") (pin "3") (pinfunction "S_3") (pintype "passive"))
    )
    (net (code "33") (name "Net-(IC3B-OUT)") (class "Default")
      (node (ref "IC3") (pin "7") (pinfunction "OUT_7") (pintype "output"))
      (node (ref "R22") (pin "1") (pinfunction "1_1") (pintype "passive"))
      (node (ref "R23") (pin "2") (pinfunction "2_2") (pintype "passive"))
    )
    (net (code "34") (name "Net-(IC4A-B1)") (class "Default")
      (node (ref "IC4") (pin "1") (pinfunction "C1_1") (pintype "passive"))
      (node (ref "IC4") (pin "2") (pinfunction "B1_2") (pintype "passive"))
      (node (ref "IC4") (pin "3") (pinfunction "E_3") (pintype "passive"))
      (node (ref "R36") (pin "2") (pinfunction "2_2") (pintype "passive"))
    )
    (net (code "35") (name "Net-(IC4A-B2)") (class "Default")
      (node (ref "IC4") (pin "4") (pinfunction "B2_4") (pintype "passive"))
      (node (ref "R30") (pin "2") (pinfunction "2_2") (pintype "passive"))
      (node (ref "R35") (pin "2") (pinfunction "2_2") (pintype "passive"))
      (node (ref "R56") (pin "1") (pinfunction "1_1") (pintype "passive"))
    )
    (net (code "36") (name "Net-(IC4A-C2)") (class "Default")
      (node (ref "IC4") (pin "5") (pinfunction "C2_5") (pintype "passive"))
      (node (ref "IC4") (pin "9") (pinfunction "B_9") (pintype "passive"))
      (node (ref "R37") (pin "1") (pinfunction "1_1") (pintype "passive"))
    )
    (net (code "37") (name "Net-(IC4B-B)") (class "Default")
      (node (ref "IC4") (pin "14") (pinfunction "C_14") (pintype "passive"))
      (node (ref "IC4") (pin "6") (pinfunction "B_6") (pintype "passive"))
      (node (ref "R42") (pin "1") (pinfunction "1_1") (pintype "passive"))
    )
    (net (code "38") (name "Net-(IC4B-C)") (class "Default")
      (node (ref "C6") (pin "2") (pinfunction "2_2") (pintype "passive"))
      (node (ref "IC4") (pin "8") (pinfunction "C_8") (pintype "passive"))
      (node (ref "IC5") (pin "1") (pinfunction "C1_1") (pintype "passive"))
      (node (ref "IC5") (pin "2") (pinfunction "B1_2") (pintype "passive"))
      (node (ref "IC5") (pin "3") (pinfunction "E_3") (pintype "passive"))
    )
    (net (code "39") (name "Net-(IC4B-E)") (class "Default")
      (node (ref "IC4") (pin "10") (pinfunction "E_10") (pintype "passive"))
      (node (ref "IC4") (pin "7") (pinfunction "E_7") (pintype "passive"))
      (node (ref "R34") (pin "1") (pinfunction "1_1") (pintype "passive"))
    )
    (net (code "40") (name "Net-(IC4C-C)") (class "Default")
      (node (ref "C6") (pin "1") (pinfunction "1_1") (pintype "passive"))
      (node (ref "IC4") (pin "11") (pinfunction "C_11") (pintype "passive"))
      (node (ref "IC5") (pin "13") (pinfunction "E_13") (pintype "passive"))
    )
    (net (code "41") (name "Net-(IC4D-B)") (class "Default")
      (node (ref "IC4") (pin "12") (pinfunction "B_12") (pintype "passive"))
      (node (ref "R102") (pin "2") (pinfunction "2_2") (pintype "passive"))
      (node (ref "R41") (pin "1") (pinfunction "1_1") (pintype "passive"))
      (node (ref "TONE") (pin "1") (pinfunction "1_1") (pintype "passive"))
    )
    (net (code "42") (name "Net-(IC4D-E)") (class "Default")
      (node (ref "IC4") (pin "13") (pinfunction "E_13") (pintype "passive"))
      (node (ref "R40") (pin "1") (pinfunction "1_1") (pintype "passive"))
    )
    (net (code "43") (name "Net-(IC5A-B2)") (class "Default")
      (node (ref "IC5") (pin "12") (pinfunction "B_12") (pintype "passive"))
      (node (ref "IC5") (pin "4") (pinfunction "B2_4") (pintype "passive"))
      (node (ref "R43") (pin "2") (pinfunction "2_2") (pintype "passive"))
      (node (ref "R44") (pin "1") (pinfunction "1_1") (pintype "passive"))
    )
    (net (code "44") (name "Net-(IC5A-C2)") (class "Default")
      (node (ref "C7") (pin "2") (pinfunction "2_2") (pintype "passive"))
      (node (ref "IC5") (pin "5") (pinfunction "C2_5") (pintype "passive"))
      (node (ref "IC5") (pin "7") (pinfunction "E_7") (pintype "passive"))
    )
    (net (code "45") (name "Net-(IC5B-B)") (class "Default")
      (node (ref "IC5") (pin "6") (pinfunction "B_6") (pintype "passive"))
      (node (ref "IC5") (pin "9") (pinfunction "B_9") (pintype "passive"))
      (node (ref "R44") (pin "2") (pinfunction "2_2") (pintype "passive"))
      (node (ref "R45") (pin "1") (pinfunction "1_1") (pintype "passive"))
    )
    (net (code "46") (name "Net-(IC5B-C)") (class "Default")
      (node (ref "C8") (pin "2") (pinfunction "2_2") (pintype "passive"))
      (node (ref "IC5") (pin "8") (pinfunction "C_8") (pintype "passive"))
      (node (ref "IC6") (pin "1") (pinfunction "C1_1") (pintype "passive"))
      (node (ref "IC6") (pin "2") (pinfunction "B1_2") (pintype "passive"))
      (node (ref "IC6") (pin "3") (pinfunction "E_3") (pintype "passive"))
    )
    (net (code "47") (name "Net-(IC5C-C)") (class "Default")
      (node (ref "C8") (pin "1") (pinfunction "1_1") (pintype "passive"))
      (node (ref "IC5") (pin "11") (pinfunction "C_11") (pintype "passive"))
      (node (ref "IC6") (pin "13") (pinfunction "E_13") (pintype "passive"))
    )
    (net (code "48") (name "Net-(IC5C-E)") (class "Default")
      (node (ref "C7") (pin "1") (pinfunction "1_1") (pintype "passive"))
      (node (ref "IC5") (pin "10") (pinfunction "E_10") (pintype "passive"))
      (node (ref "IC5") (pin "14") (pinfunction "C_14") (pintype "passive"))
    )
    (net (code "49") (name "Net-(IC6A-B2)") (class "Default")
      (node (ref "IC6") (pin "12") (pinfunction "B_12") (pintype "passive"))
      (node (ref "IC6") (pin "4") (pinfunction "B2_4") (pintype "passive"))
      (node (ref "R45") (pin "2") (pinfunction "2_2") (pintype "passive"))
      (node (ref "R46") (pin "1") (pinfunction "1_1") (pintype "passive"))
    )
    (net (code "50") (name "Net-(IC6A-C2)") (class "Default")
      (node (ref "C9") (pin "2") (pinfunction "2_2") (pintype "passive"))
      (node (ref "IC6") (pin "5") (pinfunction "C2_5") (pintype "passive"))
      (node (ref "IC6") (pin "7") (pinfunction "E_7") (pintype "passive"))
      (node (ref "T4") (pin "G") (pinfunction "G_G") (pintype "passive"))
    )
    (net (code "51") (name "Net-(IC6B-B)") (class "Default")
      (node (ref "IC6") (pin "6") (pinfunction "B_6") (pintype "passive"))
      (node (ref "IC6") (pin "9") (pinfunction "B_9") (pintype "passive"))
      (node (ref "R46") (pin "2") (pinfunction "2_2") (pintype "passive"))
      (node (ref "R47") (pin "1") (pinfunction "1_1") (pintype "passive"))
    )
    (net (code "52") (name "Net-(IC6C-E)") (class "Default")
      (node (ref "C9") (pin "1") (pinfunction "1_1") (pintype "passive"))
      (node (ref "IC6") (pin "10") (pinfunction "E_10") (pintype "passive"))
      (node (ref "IC6") (pin "14") (pinfunction "C_14") (pintype "passive"))
      (node (ref "T5") (pin "G") (pinfunction "G_G") (pintype "passive"))
    )
    (net (code "53") (name "Net-(IC7A--IN)") (class "Default")
      (node (ref "C13") (pin "1") (pinfunction "1_1") (pintype "passive"))
      (node (ref "IC7") (pin "2") (pinfunction "-IN_2") (pintype "input"))
      (node (ref "R69") (pin "1") (pinfunction "1_1") (pintype "passive"))
    )
    (net (code "54") (name "Net-(IC7A-OUT)") (class "Default")
      (node (ref "C14") (pin "2") (pinfunction "2_2") (pintype "passive"))
      (node (ref "IC7") (pin "1") (pinfunction "OUT_1") (pintype "output"))
      (node (ref "R68") (pin "1") (pinfunction "1_1") (pintype "passive"))
      (node (ref "S1") (pin "1") (pinfunction "O_1") (pintype "passive"))
      (node (ref "S2") (pin "2") (pinfunction "P_2") (pintype "passive"))
    )
    (net (code "55") (name "Net-(IC7B-+IN)") (class "Default")
      (node (ref "IC7") (pin "5") (pinfunction "+IN_5") (pintype "input"))
      (node (ref "R68") (pin "2") (pinfunction "2_2") (pintype "passive"))
      (node (ref "R70") (pin "1") (pinfunction "1_1") (pintype "passive"))
    )
    (net (code "56") (name "Net-(IC7B-OUT)") (class "Default")
      (node (ref "D4") (pin "A") (pinfunction "A_A") (pintype "passive"))
      (node (ref "IC7") (pin "7") (pinfunction "OUT_7") (pintype "output"))
      (node (ref "R67") (pin "2") (pinfunction "2_2") (pintype "passive"))
      (node (ref "R70") (pin "2") (pinfunction "2_2") (pintype "passive"))
      (node (ref "RATE") (pin "3") (pinfunction "3_3") (pintype "passive"))
    )
    (net (code "57") (name "Net-(IC7C-V+)") (class "Default")
      (node (ref "IC7") (pin "8") (pinfunction "V+_8") (pintype "power_in"))
      (node (ref "R71") (pin "1") (pinfunction "1_1") (pintype "passive"))
    )
    (net (code "58") (name "Net-(IC8-+IN)") (class "Default")
      (node (ref "IC8") (pin "3") (pinfunction "+IN_3") (pintype "input"))
      (node (ref "R62") (pin "1") (pinfunction "1_1") (pintype "passive"))
      (node (ref "R64*") (pin "1") (pinfunction "1_1") (pintype "passive"))
    )
    (net (code "59") (name "Net-(IC8--IN)") (class "Default")
      (node (ref "IC8") (pin "2") (pinfunction "-IN_2") (pintype "input"))
      (node (ref "R55") (pin "2") (pinfunction "2_2") (pintype "passive"))
      (node (ref "R65*") (pin "1") (pinfunction "1_1") (pintype "passive"))
    )
    (net (code "60") (name "Net-(IC8-OPT)") (class "Default")
      (node (ref "IC8") (pin "5") (pinfunction "OPT_5") (pintype "passive"))
      (node (ref "T7") (pin "C") (pinfunction "C_C") (pintype "passive"))
    )
    (net (code "61") (name "Net-(IC11--IN)") (class "Default")
      (node (ref "C15") (pin "1") (pinfunction "1_1") (pintype "passive"))
      (node (ref "IC11") (pin "2") (pinfunction "-IN_2") (pintype "input"))
      (node (ref "R75") (pin "2") (pinfunction "2_2") (pintype "passive"))
      (node (ref "R76") (pin "2") (pinfunction "2_2") (pintype "passive"))
    )
    (net (code "62") (name "Net-(IMPACT-Pad2)") (class "Default")
      (node (ref "IMPACT") (pin "2") (pinfunction "2_2") (pintype "passive"))
      (node (ref "R16") (pin "2") (pinfunction "2_2") (pintype "passive"))
    )
    (net (code "63") (name "Net-(NULL-S)") (class "Default")
      (node (ref "NULL") (pin "2") (pinfunction "S_2") (pintype "passive"))
      (node (ref "R30") (pin "1") (pinfunction "1_1") (pintype "passive"))
    )
    (net (code "64") (name "Net-(N_TRIG-Pad1)") (class "Default")
      (node (ref "N_TRIG") (pin "1") (pinfunction "1_1") (pintype "passive"))
      (node (ref "R*") (pin "2") (pinfunction "2_2") (pintype "passive"))
      (node (ref "R5") (pin "2") (pinfunction "2_2") (pintype "passive"))
      (node (ref "R6") (pin "1") (pinfunction "1_1") (pintype "passive"))
    )
    (net (code "65") (name "Net-(OFFSET-S)") (class "Default")
      (node (ref "OFFSET") (pin "2") (pinfunction "S_2") (pintype "passive"))
      (node (ref "R62") (pin "2") (pinfunction "2_2") (pintype "passive"))
    )
    (net (code "66") (name "Net-(OUT-Pad1)") (class "Default")
      (node (ref "OUT") (pin "1") (pinfunction "1_1") (pintype "passive"))
      (node (ref "R60") (pin "2") (pinfunction "2_2") (pintype "passive"))
      (node (ref "T6") (pin "E") (pinfunction "E_E") (pintype "passive"))
    )
    (net (code "67") (name "Net-(PITCH-Pad2)") (class "Default")
      (node (ref "PITCH") (pin "2") (pinfunction "2_2") (pintype "passive"))
      (node (ref "R107") (pin "2") (pinfunction "2_2") (pintype "passive"))
    )
    (net (code "68") (name "Net-(PITCH_CV-Pad1)") (class "Default")
      (node (ref "PITCH_CV") (pin "1") (pinfunction "1_1") (pintype "passive"))
      (node (ref "R100*") (pin "1") (pinfunction "1_1") (pintype "passive"))
    )
    (net (code "69") (name "Net-(R29-Pad1)") (class "Default")
      (node (ref "R29") (pin "1") (pinfunction "1_1") (pintype "passive"))
      (node (ref "T2") (pin "E") (pinfunction "E_E") (pintype "passive"))
      (node (ref "T3") (pin "B") (pinfunction "B_B") (pintype "passive"))
    )
    (net (code "70") (name "Net-(R32-Pad1)") (class "Default")
      (node (ref "R32") (pin "1") (pinfunction "1_1") (pintype "passive"))
      (node (ref "T7") (pin "E") (pinfunction "E_E") (pintype "passive"))
    )
    (net (code "71") (name "Net-(R34-Pad2)") (class "Default")
      (node (ref "R34") (pin "2") (pinfunction "2_2") (pintype "passive"))
      (node (ref "T3") (pin "C") (pinfunction "C_C") (pintype "passive"))
    )
    (net (code "72") (name "Net-(R36-Pad1)") (class "Default")
      (node (ref "R36") (pin "1") (pinfunction "1_1") (pintype "passive"))
      (node (ref "R38") (pin "1") (pinfunction "1_1") (pintype "passive"))
      (node (ref "R40") (pin "2") (pinfunction "2_2") (pintype "passive"))
    )
    (net (code "73") (name "Net-(R37-Pad2)") (class "Default")
      (node (ref "R37") (pin "2") (pinfunction "2_2") (pintype "passive"))
      (node (ref "R39") (pin "2") (pinfunction "2_2") (pintype "passive"))
      (node (ref "R42") (pin "2") (pinfunction "2_2") (pintype "passive"))
      (node (ref "R43") (pin "1") (pinfunction "1_1") (pintype "passive"))
    )
    (net (code "74") (name "Net-(R57-Pad1)") (class "Default")
      (node (ref "R57") (pin "1") (pinfunction "1_1") (pintype "passive"))
      (node (ref "T6") (pin "C") (pinfunction "C_C") (pintype "passive"))
    )
    (net (code "75") (name "Net-(R69-Pad2)") (class "Default")
      (node (ref "R69") (pin "2") (pinfunction "2_2") (pintype "passive"))
      (node (ref "RATE") (pin "2") (pinfunction "2_2") (pintype "passive"))
    )
    (net (code "76") (name "Net-(R73-Pad2)") (class "Default")
      (node (ref "R73") (pin "2") (pinfunction "2_2") (pintype "passive"))
      (node (ref "RATE") (pin "1") (pinfunction "1_1") (pintype "passive"))
    )
    (net (code "77") (name "Net-(R100*-Pad2)") (class "Default")
      (node (ref "R100*") (pin "2") (pinfunction "2_2") (pintype "passive"))
      (node (ref "R104") (pin "1") (pinfunction "1_1") (pintype "passive"))
      (node (ref "R23") (pin "1") (pinfunction "1_1") (pintype "passive"))
      (node (ref "R24") (pin "2") (pinfunction "2_2") (pintype "passive"))
      (node (ref "R28") (pin "1") (pinfunction "1_1") (pintype "passive"))
      (node (ref "R33") (pin "1") (pinfunction "1_1") (pintype "passive"))
      (node (ref "T2") (pin "B") (pinfunction "B_B") (pintype "passive"))
    )
    (net (code "78") (name "Net-(R100-Pad1)") (class "Default")
      (node (ref "R100") (pin "1") (pinfunction "1_1") (pintype "passive"))
      (node (ref "R56") (pin "2") (pinfunction "2_2") (pintype "passive"))
      (node (ref "TONE") (pin "3") (pinfunction "3_3") (pintype "passive"))
    )
    (net (code "79") (name "Net-(R106-Pad1)") (class "Default")
      (node (ref "R106") (pin "1") (pinfunction "1_1") (pintype "passive"))
      (node (ref "R107") (pin "1") (pinfunction "1_1") (pintype "passive"))
      (node (ref "R33") (pin "2") (pinfunction "2_2") (pintype "passive"))
    )
    (net (code "80") (name "Net-(S1-P)") (class "Default")
      (node (ref "S1") (pin "2") (pinfunction "P_2") (pintype "passive"))
      (node (ref "S3") (pin "2") (pinfunction "P_2") (pintype "passive"))
    )
    (net (code "81") (name "Net-(S1-S)") (class "Default")
      (node (ref "D4") (pin "C") (pinfunction "C_C") (pintype "passive"))
      (node (ref "S1") (pin "3") (pinfunction "S_3") (pintype "passive"))
    )
    (net (code "82") (name "Net-(S2-S)") (class "Default")
      (node (ref "C13") (pin "2") (pinfunction "2_2") (pintype "passive"))
      (node (ref "C14") (pin "1") (pinfunction "1_1") (pintype "passive"))
      (node (ref "S2") (pin "3") (pinfunction "S_3") (pintype "passive"))
    )
    (net (code "83") (name "Net-(S3-S)") (class "Default")
      (node (ref "R21") (pin "2") (pinfunction "2_2") (pintype "passive"))
      (node (ref "S3") (pin "3") (pinfunction "S_3") (pintype "passive"))
    )
    (net (code "84") (name "Net-(UP/DOWN-O)") (class "Default")
      (node (ref "R28") (pin "2") (pinfunction "2_2") (pintype "passive"))
      (node (ref "UP/DOWN") (pin "1") (pinfunction "O_1") (pintype "passive"))
    )
    (net (code "85") (name "Net-(UP/DOWN-P)") (class "Default")
      (node (ref "R27") (pin "1") (pinfunction "1_1") (pintype "passive"))
      (node (ref "UP/DOWN") (pin "2") (pinfunction "P_2") (pintype "passive"))
    )
    (net (code "86") (name "Net-(X1A-S)") (class "Default")
      (node (ref "J3") (pin "1") (pinfunction "1_1") (pintype "passive"))
      (node (ref "L1") (pin "1") (pinfunction "1_1") (pintype "passive"))
      (node (ref "X1") (pin "1") (pinfunction "S_1") (pintype "passive"))
      (node (ref "X1") (pin "2") (pinfunction "S_2") (pintype "passive"))
    )
    (net (code "87") (name "Net-(X1B-S)") (class "Default")
      (node (ref "J3") (pin "4") (pinfunction "4_4") (pintype "passive"))
      (node (ref "L2") (pin "1") (pinfunction "1_1") (pintype "passive"))
      (node (ref "X1") (pin "10") (pinfunction "S_10") (pintype "passive"))
      (node (ref "X1") (pin "9") (pinfunction "S_9") (pintype "passive"))
    )
    (net (code "88") (name "unconnected-(IC8-ON1-Pad1)") (class "Default")
      (node (ref "IC8") (pin "1") (pinfunction "ON1_1") (pintype "passive"))
    )
    (net (code "89") (name "unconnected-(IC8-ON2-Pad8)") (class "Default")
      (node (ref "IC8") (pin "8") (pinfunction "ON2_8") (pintype "passive"))
    )
    (net (code "90") (name "unconnected-(IC11-CMP-Pad8)") (class "Default")
      (node (ref "IC11") (pin "8") (pinfunction "CMP_8") (pintype "passive"))
    )
    (net (code "91") (name "unconnected-(IC11-ON-Pad5)") (class "Default")
      (node (ref "IC11") (pin "5") (pinfunction "ON_5") (pintype "passive"))
    )
    (net (code "92") (name "unconnected-(IC11-ON{slash}CMP-Pad1)") (class "Default")
      (node (ref "IC11") (pin "1") (pinfunction "ON/CMP_1") (pintype "passive"))
    )
    (net (code "93") (name "unconnected-(S2-O-Pad1)") (class "Default")
      (node (ref "S2") (pin "1") (pinfunction "O_1") (pintype "passive"))
    )
    (net (code "94") (name "unconnected-(S3-O-Pad1)") (class "Default")
      (node (ref "S3") (pin "1") (pinfunction "O_1") (pintype "passive"))
    )
    (net (code "95") (name "unconnected-(T8-PadB)") (class "Default")
      (node (ref "T8") (pin "B") (pinfunction "B_B") (pintype "passive"))
    )
  )
)
